# DAC.net
KiCad netlist of a schematic drawn in Altium Designer
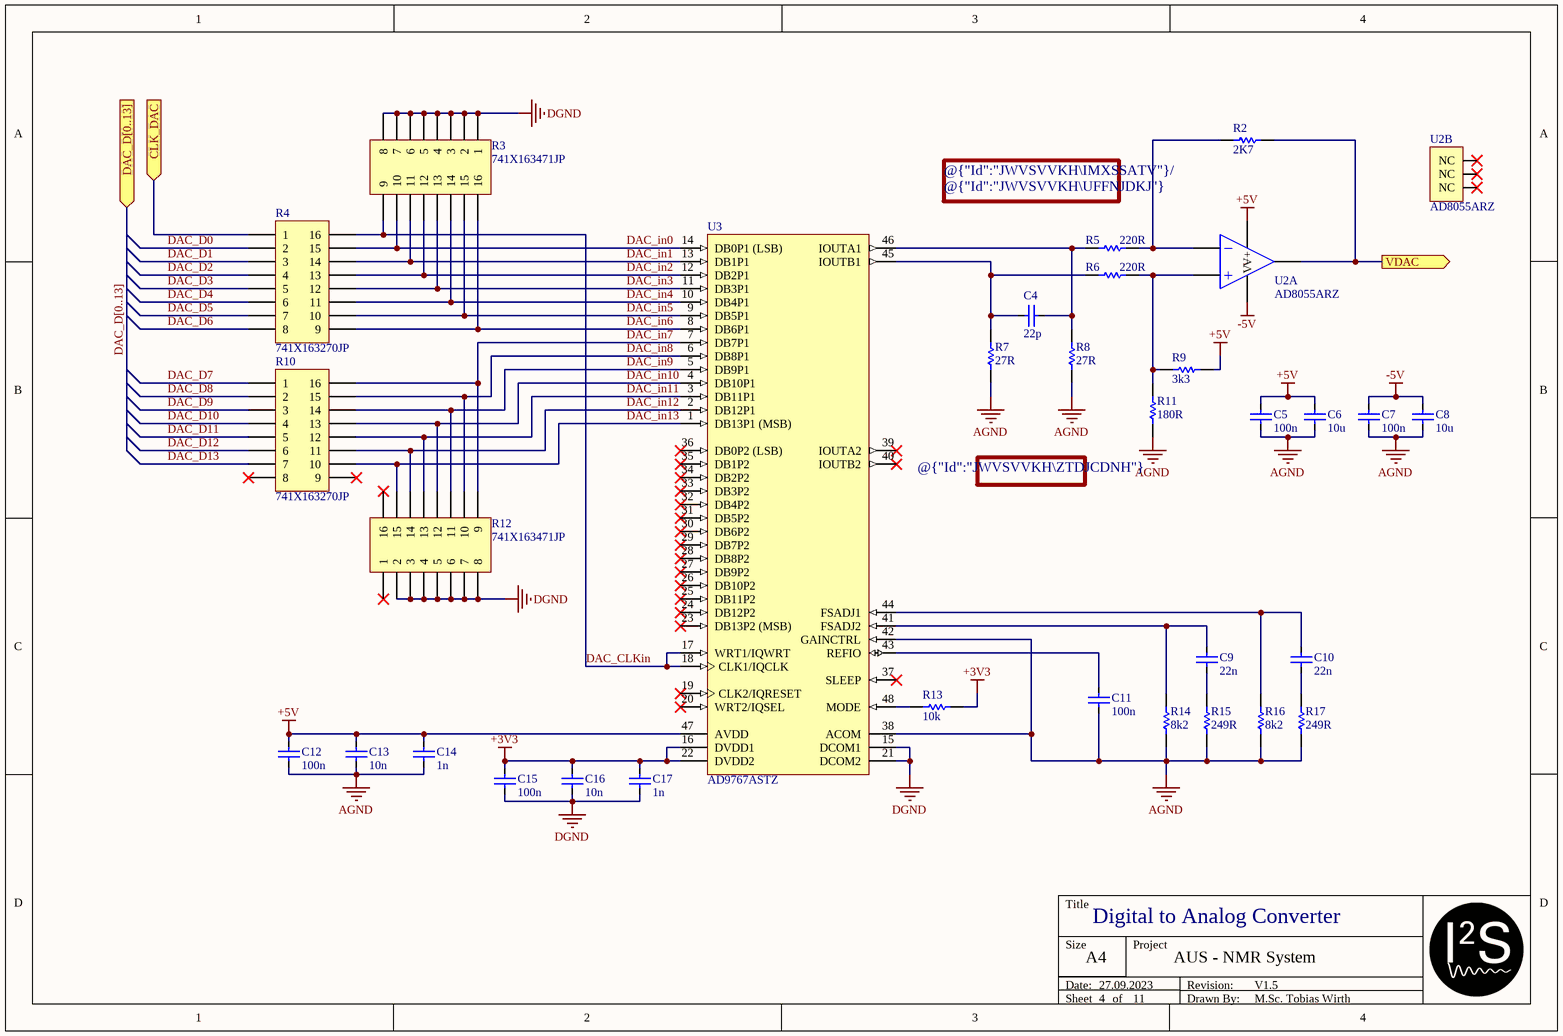
[diagram p0: DAC.SchDoc]

(export (version "E")
  (design (tool "Eeschema 10.0.6"))
  (components
    (comp (ref "C4") (value "22p") (footprint "CAP_0402") (libsource (lib "IIS-Lib_TW") (part "Cap")))
    (comp (ref "C5") (value "100n") (footprint "CAP_0402") (libsource (lib "IIS-Lib_TW") (part "Cap")))
    (comp (ref "C6") (value "10u") (footprint "CAP_0603") (libsource (lib "IIS-Lib_TW") (part "Cap")))
    (comp (ref "C7") (value "100n") (footprint "CAP_0402") (libsource (lib "IIS-Lib_TW") (part "Cap")))
    (comp (ref "C8") (value "10u") (footprint "CAP_0603") (libsource (lib "IIS-Lib_TW") (part "Cap")))
    (comp (ref "C9") (value "22n") (footprint "CAP_0402") (libsource (lib "IIS-Lib_TW") (part "Cap")))
    (comp (ref "C10") (value "22n") (footprint "CAP_0402") (libsource (lib "IIS-Lib_TW") (part "Cap")))
    (comp (ref "C11") (value "100n") (footprint "CAP_0402") (libsource (lib "IIS-Lib_TW") (part "Cap")))
    (comp (ref "C12") (value "100n") (footprint "CAP_0402") (libsource (lib "IIS-Lib_TW") (part "Cap")))
    (comp (ref "C13") (value "10n") (footprint "CAP_0402") (libsource (lib "IIS-Lib_TW") (part "Cap")))
    (comp (ref "C14") (value "1n") (footprint "CAP_0402") (libsource (lib "IIS-Lib_TW") (part "Cap")))
    (comp (ref "C15") (value "100n") (footprint "CAP_0402") (libsource (lib "IIS-Lib_TW") (part "Cap")))
    (comp (ref "C16") (value "10n") (footprint "CAP_0402") (libsource (lib "IIS-Lib_TW") (part "Cap")))
    (comp (ref "C17") (value "1n") (footprint "CAP_0402") (libsource (lib "IIS-Lib_TW") (part "Cap")))
    (comp (ref "R2") (value "2K7") (footprint "RES_0402") (libsource (lib "IIS-Lib_TW") (part "Res")))
    (comp (ref "R3")
      (value "741X163471JP")
      (footprint "741X163")
      (description "Isolated 8 Resistor Network/Array, Convex, Long Side Terminals")
      (libsource (lib "") (part "741X163_1"))
    )
    (comp (ref "R4")
      (value "741X163270JP")
      (footprint "741X163")
      (description "Isolated 8 Resistor Network/Array, Convex, Long Side Terminals")
      (libsource (lib "IIS-Lib_TW") (part "741X163"))
    )
    (comp (ref "R5") (value "220R") (footprint "RES_0402") (libsource (lib "IIS-Lib_TW") (part "Res")))
    (comp (ref "R6") (value "220R") (footprint "RES_0402") (libsource (lib "IIS-Lib_TW") (part "Res")))
    (comp (ref "R7") (value "27R") (footprint "RES_0402") (libsource (lib "IIS-Lib_TW") (part "Res")))
    (comp (ref "R8") (value "27R") (footprint "RES_0402") (libsource (lib "IIS-Lib_TW") (part "Res")))
    (comp (ref "R9") (value "3k3") (footprint "RES_0402") (libsource (lib "IIS-Lib_TW") (part "Res")))
    (comp (ref "R10")
      (value "741X163270JP")
      (footprint "741X163")
      (description "Isolated 8 Resistor Network/Array, Convex, Long Side Terminals")
      (libsource (lib "IIS-Lib_TW") (part "741X163"))
    )
    (comp (ref "R11") (value "180R") (footprint "RES_0402") (libsource (lib "IIS-Lib_TW") (part "Res")))
    (comp (ref "R12")
      (value "741X163471JP")
      (footprint "741X163")
      (description "Isolated 8 Resistor Network/Array, Convex, Long Side Terminals")
      (libsource (lib "") (part "741X163_2"))
    )
    (comp (ref "R13") (value "10k") (footprint "RES_0402") (libsource (lib "IIS-Lib_TW") (part "Res")))
    (comp (ref "R14") (value "8k2") (footprint "RES_0402") (libsource (lib "IIS-Lib_TW") (part "Res")))
    (comp (ref "R15") (value "249R") (footprint "RES_0402") (libsource (lib "IIS-Lib_TW") (part "Res")))
    (comp (ref "R16") (value "8k2") (footprint "RES_0402") (libsource (lib "IIS-Lib_TW") (part "Res")))
    (comp (ref "R17") (value "249R") (footprint "RES_0402") (libsource (lib "IIS-Lib_TW") (part "Res")))
    (comp (ref "U2")
      (value "AD8055ARZ")
      (footprint "SOIC127P600X175-8N")
      (description "300 MHz Voltage Feedback Amplifier")
      (libsource (lib "IIS-Lib_TW") (part "AD8055"))
    )
    (comp (ref "U3")
      (value "AD9767ASTZ")
      (footprint "TQFP-48_L")
      (description "Dual 14-Bit TxDAC+, 125 Msps, -40 to +85 degC, ST-48, Pb-Free, Tray")
      (fields (field (name "GENERIC PART NUMBER") "AD9767") (field (name "MANUFACTURER") "Analog Devices"))
      (libsource (lib "IIS-Lib_TW") (part "AD9767"))
    )
  )
  (nets
    (net (code "1") (name "+3V3") (class "Default")
      (node (ref "C15") (pin "1") (pinfunction "1_1") (pintype "passive"))
      (node (ref "C16") (pin "1") (pinfunction "1_1") (pintype "passive"))
      (node (ref "C17") (pin "1") (pinfunction "1_1") (pintype "passive"))
      (node (ref "R13") (pin "1") (pinfunction "1_1") (pintype "passive"))
      (node (ref "U3") (pin "16") (pinfunction "DVDD1_16") (pintype "power_in"))
      (node (ref "U3") (pin "22") (pinfunction "DVDD2_22") (pintype "power_in"))
    )
    (net (code "2") (name "+5V") (class "Default")
      (node (ref "C12") (pin "1") (pinfunction "1_1") (pintype "passive"))
      (node (ref "C13") (pin "1") (pinfunction "1_1") (pintype "passive"))
      (node (ref "C14") (pin "1") (pinfunction "1_1") (pintype "passive"))
      (node (ref "C5") (pin "1") (pinfunction "1_1") (pintype "passive"))
      (node (ref "C6") (pin "1") (pinfunction "1_1") (pintype "passive"))
      (node (ref "R9") (pin "1") (pinfunction "1_1") (pintype "passive"))
      (node (ref "U2") (pin "7") (pinfunction "V+_7") (pintype "passive"))
      (node (ref "U3") (pin "47") (pinfunction "AVDD_47") (pintype "power_in"))
    )
    (net (code "3") (name "-5V") (class "Default")
      (node (ref "C7") (pin "1") (pinfunction "1_1") (pintype "passive"))
      (node (ref "C8") (pin "1") (pinfunction "1_1") (pintype "passive"))
      (node (ref "U2") (pin "4") (pinfunction "V−_4") (pintype "passive"))
    )
    (net (code "5") (name "/CLK_DAC") (class "Default")
      (node (ref "R4") (pin "1") (pinfunction "1_1") (pintype "passive"))
    )
    (net (code "6") (name "/DAC_CLKin") (class "Default")
      (node (ref "R3") (pin "9") (pinfunction "9_9") (pintype "passive"))
      (node (ref "R4") (pin "16") (pinfunction "16_16") (pintype "passive"))
      (node (ref "U3") (pin "17") (pinfunction "WRT1/IQWRT_17") (pintype "input"))
      (node (ref "U3") (pin "18") (pinfunction "CLK1/IQCLK_18") (pintype "input"))
    )
    (net (code "7") (name "/DAC_D0") (class "Default")
      (node (ref "R4") (pin "2") (pinfunction "2_2") (pintype "passive"))
    )
    (net (code "8") (name "/DAC_D1") (class "Default")
      (node (ref "R4") (pin "3") (pinfunction "3_3") (pintype "passive"))
    )
    (net (code "9") (name "/DAC_D2") (class "Default")
      (node (ref "R4") (pin "4") (pinfunction "4_4") (pintype "passive"))
    )
    (net (code "10") (name "/DAC_D3") (class "Default")
      (node (ref "R4") (pin "5") (pinfunction "5_5") (pintype "passive"))
    )
    (net (code "11") (name "/DAC_D4") (class "Default")
      (node (ref "R4") (pin "6") (pinfunction "6_6") (pintype "passive"))
    )
    (net (code "12") (name "/DAC_D5") (class "Default")
      (node (ref "R4") (pin "7") (pinfunction "7_7") (pintype "passive"))
    )
    (net (code "13") (name "/DAC_D6") (class "Default")
      (node (ref "R4") (pin "8") (pinfunction "8_8") (pintype "passive"))
    )
    (net (code "14") (name "/DAC_D7") (class "Default")
      (node (ref "R10") (pin "1") (pinfunction "1_1") (pintype "passive"))
    )
    (net (code "15") (name "/DAC_D8") (class "Default")
      (node (ref "R10") (pin "2") (pinfunction "2_2") (pintype "passive"))
    )
    (net (code "16") (name "/DAC_D9") (class "Default")
      (node (ref "R10") (pin "3") (pinfunction "3_3") (pintype "passive"))
    )
    (net (code "17") (name "/DAC_D10") (class "Default")
      (node (ref "R10") (pin "4") (pinfunction "4_4") (pintype "passive"))
    )
    (net (code "18") (name "/DAC_D11") (class "Default")
      (node (ref "R10") (pin "5") (pinfunction "5_5") (pintype "passive"))
    )
    (net (code "19") (name "/DAC_D12") (class "Default")
      (node (ref "R10") (pin "6") (pinfunction "6_6") (pintype "passive"))
    )
    (net (code "20") (name "/DAC_D13") (class "Default")
      (node (ref "R10") (pin "7") (pinfunction "7_7") (pintype "passive"))
    )
    (net (code "22") (name "/DAC_in0") (class "Default")
      (node (ref "R3") (pin "10") (pinfunction "10_10") (pintype "passive"))
      (node (ref "R4") (pin "15") (pinfunction "15_15") (pintype "passive"))
      (node (ref "U3") (pin "14") (pinfunction "DB0P1_(LSB)_14") (pintype "input"))
    )
    (net (code "23") (name "/DAC_in1") (class "Default")
      (node (ref "R3") (pin "11") (pinfunction "11_11") (pintype "passive"))
      (node (ref "R4") (pin "14") (pinfunction "14_14") (pintype "passive"))
      (node (ref "U3") (pin "13") (pinfunction "DB1P1_13") (pintype "input"))
    )
    (net (code "24") (name "/DAC_in2") (class "Default")
      (node (ref "R3") (pin "12") (pinfunction "12_12") (pintype "passive"))
      (node (ref "R4") (pin "13") (pinfunction "13_13") (pintype "passive"))
      (node (ref "U3") (pin "12") (pinfunction "DB2P1_12") (pintype "input"))
    )
    (net (code "25") (name "/DAC_in3") (class "Default")
      (node (ref "R3") (pin "13") (pinfunction "13_13") (pintype "passive"))
      (node (ref "R4") (pin "12") (pinfunction "12_12") (pintype "passive"))
      (node (ref "U3") (pin "11") (pinfunction "DB3P1_11") (pintype "input"))
    )
    (net (code "26") (name "/DAC_in4") (class "Default")
      (node (ref "R3") (pin "14") (pinfunction "14_14") (pintype "passive"))
      (node (ref "R4") (pin "11") (pinfunction "11_11") (pintype "passive"))
      (node (ref "U3") (pin "10") (pinfunction "DB4P1_10") (pintype "input"))
    )
    (net (code "27") (name "/DAC_in5") (class "Default")
      (node (ref "R3") (pin "15") (pinfunction "15_15") (pintype "passive"))
      (node (ref "R4") (pin "10") (pinfunction "10_10") (pintype "passive"))
      (node (ref "U3") (pin "9") (pinfunction "DB5P1_9") (pintype "input"))
    )
    (net (code "28") (name "/DAC_in6") (class "Default")
      (node (ref "R3") (pin "16") (pinfunction "16_16") (pintype "passive"))
      (node (ref "R4") (pin "9") (pinfunction "9_9") (pintype "passive"))
      (node (ref "U3") (pin "8") (pinfunction "DB6P1_8") (pintype "input"))
    )
    (net (code "29") (name "/DAC_in7") (class "Default")
      (node (ref "R10") (pin "16") (pinfunction "16_16") (pintype "passive"))
      (node (ref "R12") (pin "9") (pinfunction "9_9") (pintype "passive"))
      (node (ref "U3") (pin "7") (pinfunction "DB7P1_7") (pintype "input"))
    )
    (net (code "30") (name "/DAC_in8") (class "Default")
      (node (ref "R10") (pin "15") (pinfunction "15_15") (pintype "passive"))
      (node (ref "R12") (pin "10") (pinfunction "10_10") (pintype "passive"))
      (node (ref "U3") (pin "6") (pinfunction "DB8P1_6") (pintype "input"))
    )
    (net (code "31") (name "/DAC_in9") (class "Default")
      (node (ref "R10") (pin "14") (pinfunction "14_14") (pintype "passive"))
      (node (ref "R12") (pin "11") (pinfunction "11_11") (pintype "passive"))
      (node (ref "U3") (pin "5") (pinfunction "DB9P1_5") (pintype "input"))
    )
    (net (code "32") (name "/DAC_in10") (class "Default")
      (node (ref "R10") (pin "13") (pinfunction "13_13") (pintype "passive"))
      (node (ref "R12") (pin "12") (pinfunction "12_12") (pintype "passive"))
      (node (ref "U3") (pin "4") (pinfunction "DB10P1_4") (pintype "input"))
    )
    (net (code "33") (name "/DAC_in11") (class "Default")
      (node (ref "R10") (pin "12") (pinfunction "12_12") (pintype "passive"))
      (node (ref "R12") (pin "13") (pinfunction "13_13") (pintype "passive"))
      (node (ref "U3") (pin "3") (pinfunction "DB11P1_3") (pintype "input"))
    )
    (net (code "34") (name "/DAC_in12") (class "Default")
      (node (ref "R10") (pin "11") (pinfunction "11_11") (pintype "passive"))
      (node (ref "R12") (pin "14") (pinfunction "14_14") (pintype "passive"))
      (node (ref "U3") (pin "2") (pinfunction "DB12P1_2") (pintype "input"))
    )
    (net (code "35") (name "/DAC_in13") (class "Default")
      (node (ref "R10") (pin "10") (pinfunction "10_10") (pintype "passive"))
      (node (ref "R12") (pin "15") (pinfunction "15_15") (pintype "passive"))
      (node (ref "U3") (pin "1") (pinfunction "DB13P1_(MSB)_1") (pintype "input"))
    )
    (net (code "36") (name "/VDAC") (class "Default")
      (node (ref "R2") (pin "2") (pinfunction "2_2") (pintype "passive"))
      (node (ref "U2") (pin "6") (pinfunction "6_6") (pintype "passive"))
    )
    (net (code "37") (name "AGND") (class "Default")
      (node (ref "C11") (pin "2") (pinfunction "2_2") (pintype "passive"))
      (node (ref "C12") (pin "2") (pinfunction "2_2") (pintype "passive"))
      (node (ref "C13") (pin "2") (pinfunction "2_2") (pintype "passive"))
      (node (ref "C14") (pin "2") (pinfunction "2_2") (pintype "passive"))
      (node (ref "C5") (pin "2") (pinfunction "2_2") (pintype "passive"))
      (node (ref "C6") (pin "2") (pinfunction "2_2") (pintype "passive"))
      (node (ref "C7") (pin "2") (pinfunction "2_2") (pintype "passive"))
      (node (ref "C8") (pin "2") (pinfunction "2_2") (pintype "passive"))
      (node (ref "R11") (pin "1") (pinfunction "1_1") (pintype "passive"))
      (node (ref "R14") (pin "1") (pinfunction "1_1") (pintype "passive"))
      (node (ref "R15") (pin "1") (pinfunction "1_1") (pintype "passive"))
      (node (ref "R16") (pin "1") (pinfunction "1_1") (pintype "passive"))
      (node (ref "R17") (pin "1") (pinfunction "1_1") (pintype "passive"))
      (node (ref "R7") (pin "1") (pinfunction "1_1") (pintype "passive"))
      (node (ref "R8") (pin "1") (pinfunction "1_1") (pintype "passive"))
      (node (ref "U3") (pin "38") (pinfunction "ACOM_38") (pintype "power_in"))
      (node (ref "U3") (pin "42") (pinfunction "GAINCTRL_42") (pintype "input"))
    )
    (net (code "38") (name "DGND") (class "Default")
      (node (ref "C15") (pin "2") (pinfunction "2_2") (pintype "passive"))
      (node (ref "C16") (pin "2") (pinfunction "2_2") (pintype "passive"))
      (node (ref "C17") (pin "2") (pinfunction "2_2") (pintype "passive"))
      (node (ref "R12") (pin "2") (pinfunction "2_2") (pintype "passive"))
      (node (ref "R12") (pin "3") (pinfunction "3_3") (pintype "passive"))
      (node (ref "R12") (pin "4") (pinfunction "4_4") (pintype "passive"))
      (node (ref "R12") (pin "5") (pinfunction "5_5") (pintype "passive"))
      (node (ref "R12") (pin "6") (pinfunction "6_6") (pintype "passive"))
      (node (ref "R12") (pin "7") (pinfunction "7_7") (pintype "passive"))
      (node (ref "R12") (pin "8") (pinfunction "8_8") (pintype "passive"))
      (node (ref "R3") (pin "1") (pinfunction "1_1") (pintype "passive"))
      (node (ref "R3") (pin "2") (pinfunction "2_2") (pintype "passive"))
      (node (ref "R3") (pin "3") (pinfunction "3_3") (pintype "passive"))
      (node (ref "R3") (pin "4") (pinfunction "4_4") (pintype "passive"))
      (node (ref "R3") (pin "5") (pinfunction "5_5") (pintype "passive"))
      (node (ref "R3") (pin "6") (pinfunction "6_6") (pintype "passive"))
      (node (ref "R3") (pin "7") (pinfunction "7_7") (pintype "passive"))
      (node (ref "R3") (pin "8") (pinfunction "8_8") (pintype "passive"))
      (node (ref "U3") (pin "15") (pinfunction "DCOM1_15") (pintype "power_in"))
      (node (ref "U3") (pin "21") (pinfunction "DCOM2_21") (pintype "power_in"))
    )
    (net (code "39") (name "Net-(C9-Pad2)") (class "Default")
      (node (ref "C9") (pin "2") (pinfunction "2_2") (pintype "passive"))
      (node (ref "R15") (pin "2") (pinfunction "2_2") (pintype "passive"))
    )
    (net (code "40") (name "Net-(C10-Pad2)") (class "Default")
      (node (ref "C10") (pin "2") (pinfunction "2_2") (pintype "passive"))
      (node (ref "R17") (pin "2") (pinfunction "2_2") (pintype "passive"))
    )
    (net (code "41") (name "Net-(U2A-+)") (class "Default")
      (node (ref "R11") (pin "2") (pinfunction "2_2") (pintype "passive"))
      (node (ref "R6") (pin "1") (pinfunction "1_1") (pintype "passive"))
      (node (ref "R9") (pin "2") (pinfunction "2_2") (pintype "passive"))
      (node (ref "U2") (pin "3") (pinfunction "+_3") (pintype "passive"))
    )
    (net (code "42") (name "Net-(U2A-−)") (class "Default")
      (node (ref "R2") (pin "1") (pinfunction "1_1") (pintype "passive"))
      (node (ref "R5") (pin "1") (pinfunction "1_1") (pintype "passive"))
      (node (ref "U2") (pin "2") (pinfunction "−_2") (pintype "passive"))
    )
    (net (code "43") (name "Net-(U3-FSADJ1)") (class "Default")
      (node (ref "C10") (pin "1") (pinfunction "1_1") (pintype "passive"))
      (node (ref "R16") (pin "2") (pinfunction "2_2") (pintype "passive"))
      (node (ref "U3") (pin "44") (pinfunction "FSADJ1_44") (pintype "input"))
    )
    (net (code "44") (name "Net-(U3-FSADJ2)") (class "Default")
      (node (ref "C9") (pin "1") (pinfunction "1_1") (pintype "passive"))
      (node (ref "R14") (pin "2") (pinfunction "2_2") (pintype "passive"))
      (node (ref "U3") (pin "41") (pinfunction "FSADJ2_41") (pintype "input"))
    )
    (net (code "45") (name "Net-(U3-IOUTA1)") (class "Default")
      (node (ref "C4") (pin "1") (pinfunction "1_1") (pintype "passive"))
      (node (ref "R5") (pin "2") (pinfunction "2_2") (pintype "passive"))
      (node (ref "R8") (pin "2") (pinfunction "2_2") (pintype "passive"))
      (node (ref "U3") (pin "46") (pinfunction "IOUTA1_46") (pintype "output"))
    )
    (net (code "46") (name "Net-(U3-IOUTB1)") (class "Default")
      (node (ref "C4") (pin "2") (pinfunction "2_2") (pintype "passive"))
      (node (ref "R6") (pin "2") (pinfunction "2_2") (pintype "passive"))
      (node (ref "R7") (pin "2") (pinfunction "2_2") (pintype "passive"))
      (node (ref "U3") (pin "45") (pinfunction "IOUTB1_45") (pintype "output"))
    )
    (net (code "47") (name "Net-(U3-MODE)") (class "Default")
      (node (ref "R13") (pin "2") (pinfunction "2_2") (pintype "passive"))
      (node (ref "U3") (pin "48") (pinfunction "MODE_48") (pintype "input"))
    )
    (net (code "48") (name "Net-(U3-REFIO)") (class "Default")
      (node (ref "C11") (pin "1") (pinfunction "1_1") (pintype "passive"))
      (node (ref "U3") (pin "43") (pinfunction "REFIO_43") (pintype "bidirectional"))
    )
    (net (code "49") (name "unconnected-(R10-Pad8)") (class "Default")
      (node (ref "R10") (pin "8") (pinfunction "8_8") (pintype "passive+no_connect"))
    )
    (net (code "50") (name "unconnected-(R10-Pad9)") (class "Default")
      (node (ref "R10") (pin "9") (pinfunction "9_9") (pintype "passive+no_connect"))
    )
    (net (code "51") (name "unconnected-(R12-Pad1)") (class "Default")
      (node (ref "R12") (pin "1") (pinfunction "1_1") (pintype "passive+no_connect"))
    )
    (net (code "52") (name "unconnected-(R12-Pad16)") (class "Default")
      (node (ref "R12") (pin "16") (pinfunction "16_16") (pintype "passive+no_connect"))
    )
    (net (code "53") (name "unconnected-(U2B-NC-Pad1)") (class "Default")
      (node (ref "U2") (pin "1") (pinfunction "NC_1") (pintype "passive+no_connect"))
    )
    (net (code "54") (name "unconnected-(U2B-NC-Pad5)") (class "Default")
      (node (ref "U2") (pin "5") (pinfunction "NC_5") (pintype "passive+no_connect"))
    )
    (net (code "55") (name "unconnected-(U2B-NC-Pad8)") (class "Default")
      (node (ref "U2") (pin "8") (pinfunction "NC_8") (pintype "passive+no_connect"))
    )
    (net (code "56") (name "unconnected-(U3-CLK2{slash}IQRESET-Pad19)") (class "Default")
      (node (ref "U3") (pin "19") (pinfunction "CLK2/IQRESET_19") (pintype "input+no_connect"))
    )
    (net (code "57") (name "unconnected-(U3-DB0P2_(LSB)-Pad36)") (class "Default")
      (node (ref "U3") (pin "36") (pinfunction "DB0P2_(LSB)_36") (pintype "input+no_connect"))
    )
    (net (code "58") (name "unconnected-(U3-DB1P2-Pad35)") (class "Default")
      (node (ref "U3") (pin "35") (pinfunction "DB1P2_35") (pintype "input+no_connect"))
    )
    (net (code "59") (name "unconnected-(U3-DB2P2-Pad34)") (class "Default")
      (node (ref "U3") (pin "34") (pinfunction "DB2P2_34") (pintype "input+no_connect"))
    )
    (net (code "60") (name "unconnected-(U3-DB3P2-Pad33)") (class "Default")
      (node (ref "U3") (pin "33") (pinfunction "DB3P2_33") (pintype "input+no_connect"))
    )
    (net (code "61") (name "unconnected-(U3-DB4P2-Pad32)") (class "Default")
      (node (ref "U3") (pin "32") (pinfunction "DB4P2_32") (pintype "input+no_connect"))
    )
    (net (code "62") (name "unconnected-(U3-DB5P2-Pad31)") (class "Default")
      (node (ref "U3") (pin "31") (pinfunction "DB5P2_31") (pintype "input+no_connect"))
    )
    (net (code "63") (name "unconnected-(U3-DB6P2-Pad30)") (class "Default")
      (node (ref "U3") (pin "30") (pinfunction "DB6P2_30") (pintype "input+no_connect"))
    )
    (net (code "64") (name "unconnected-(U3-DB7P2-Pad29)") (class "Default")
      (node (ref "U3") (pin "29") (pinfunction "DB7P2_29") (pintype "input+no_connect"))
    )
    (net (code "65") (name "unconnected-(U3-DB8P2-Pad28)") (class "Default")
      (node (ref "U3") (pin "28") (pinfunction "DB8P2_28") (pintype "input+no_connect"))
    )
    (net (code "66") (name "unconnected-(U3-DB9P2-Pad27)") (class "Default")
      (node (ref "U3") (pin "27") (pinfunction "DB9P2_27") (pintype "input+no_connect"))
    )
    (net (code "67") (name "unconnected-(U3-DB10P2-Pad26)") (class "Default")
      (node (ref "U3") (pin "26") (pinfunction "DB10P2_26") (pintype "input+no_connect"))
    )
    (net (code "68") (name "unconnected-(U3-DB11P2-Pad25)") (class "Default")
      (node (ref "U3") (pin "25") (pinfunction "DB11P2_25") (pintype "input+no_connect"))
    )
    (net (code "69") (name "unconnected-(U3-DB12P2-Pad24)") (class "Default")
      (node (ref "U3") (pin "24") (pinfunction "DB12P2_24") (pintype "input+no_connect"))
    )
    (net (code "70") (name "unconnected-(U3-DB13P2_(MSB)-Pad23)") (class "Default")
      (node (ref "U3") (pin "23") (pinfunction "DB13P2_(MSB)_23") (pintype "input+no_connect"))
    )
    (net (code "71") (name "unconnected-(U3-IOUTA2-Pad39)") (class "Default")
      (node (ref "U3") (pin "39") (pinfunction "IOUTA2_39") (pintype "output+no_connect"))
    )
    (net (code "72") (name "unconnected-(U3-IOUTB2-Pad40)") (class "Default")
      (node (ref "U3") (pin "40") (pinfunction "IOUTB2_40") (pintype "output+no_connect"))
    )
    (net (code "73") (name "unconnected-(U3-SLEEP-Pad37)") (class "Default")
      (node (ref "U3") (pin "37") (pinfunction "SLEEP_37") (pintype "input+no_connect"))
    )
    (net (code "74") (name "unconnected-(U3-WRT2{slash}IQSEL-Pad20)") (class "Default")
      (node (ref "U3") (pin "20") (pinfunction "WRT2/IQSEL_20") (pintype "input+no_connect"))
    )
  )
)
